# ESP32_with_USBC.net
KiCad netlist of a schematic drawn in Altium Designer
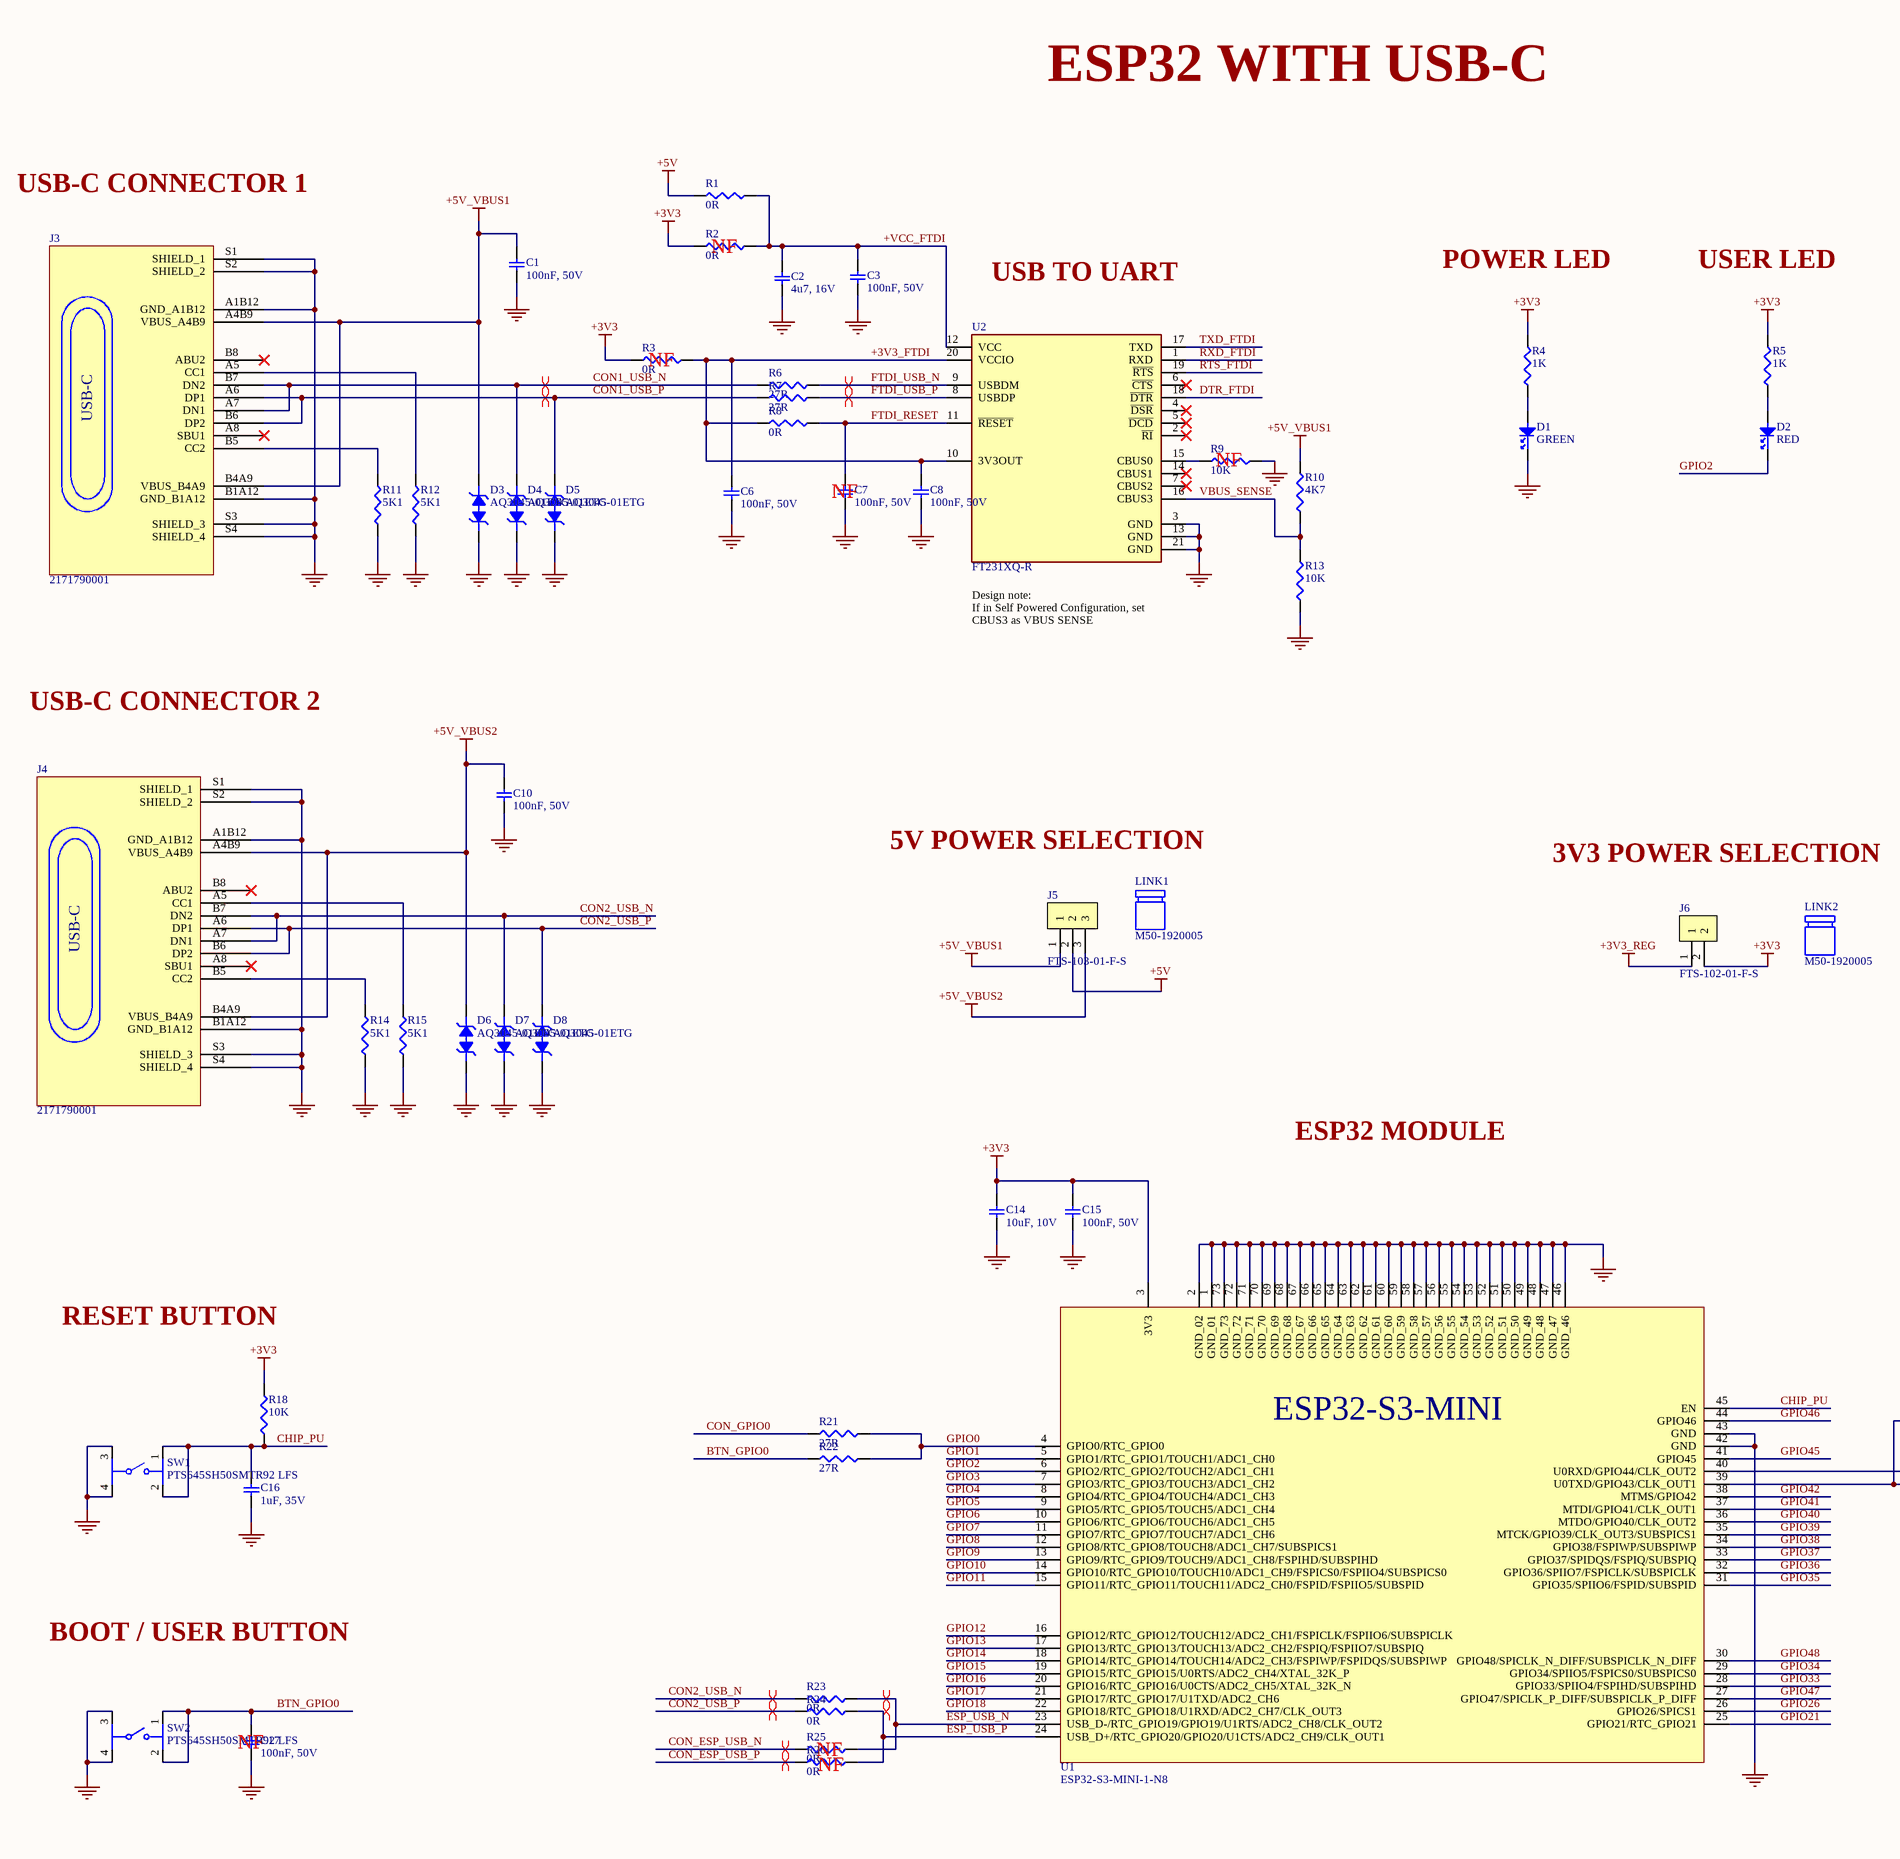
[diagram p0: ESP32 with USBC.SchDoc, left]
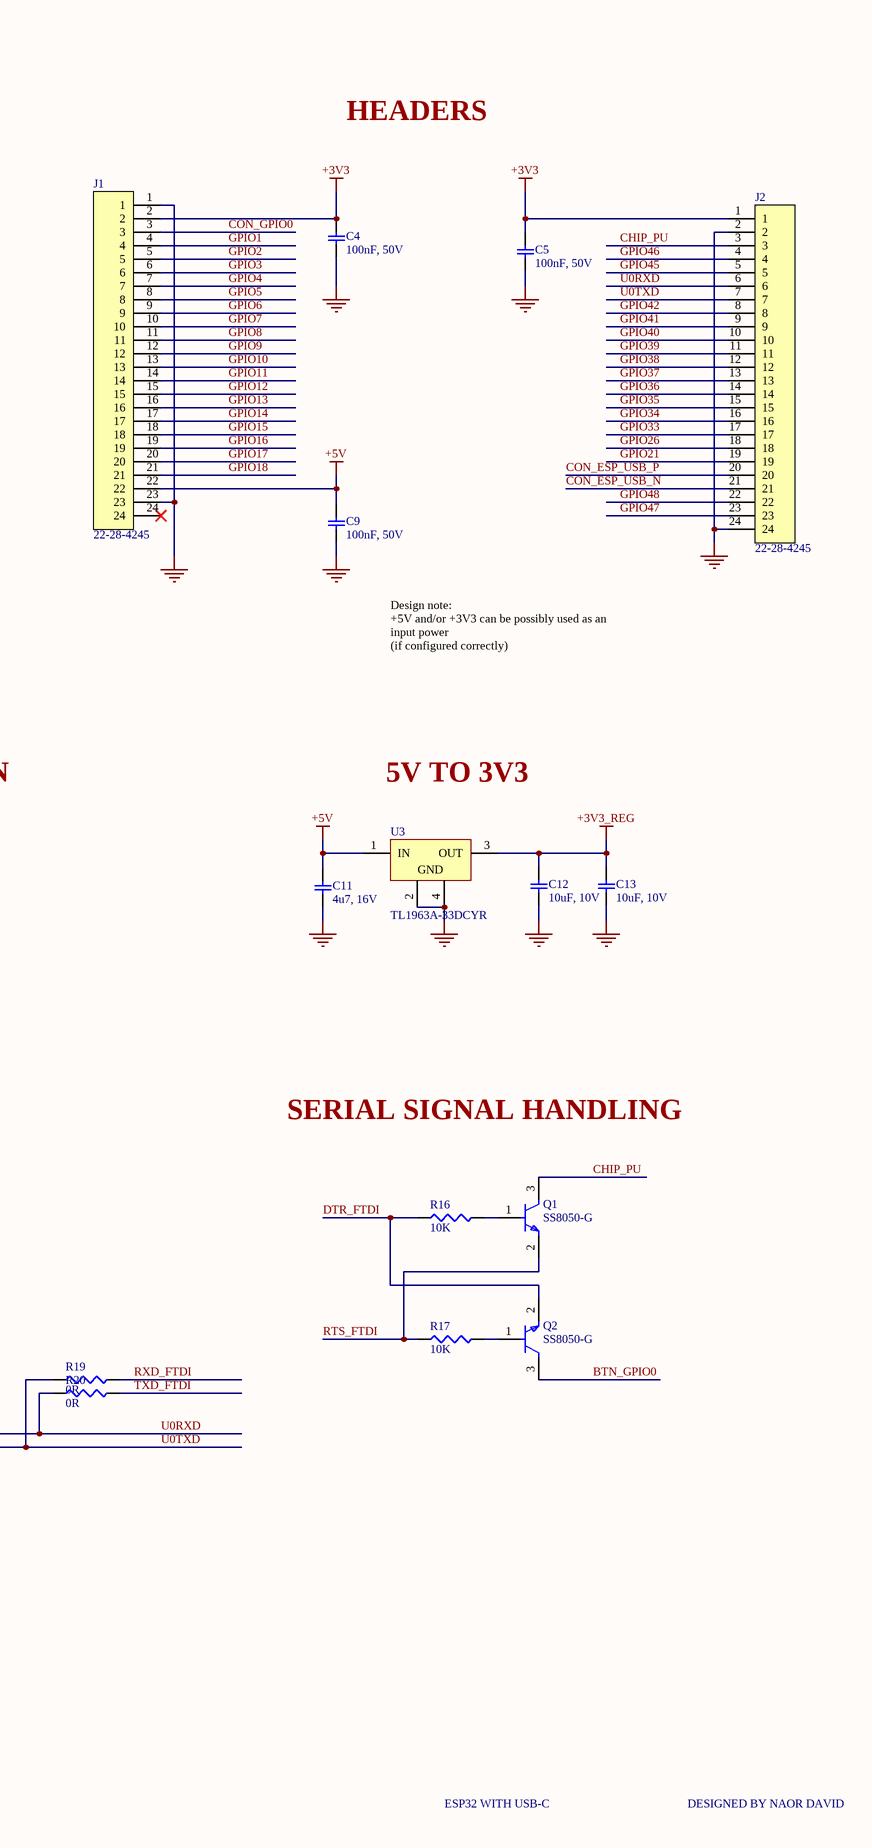
[diagram p1: ESP32 with USBC.SchDoc, right]

(export (version "E")
  (design (tool "Eeschema 10.0.6"))
  (components
    (comp (ref "C1")
      (value "100nF, 50V")
      (footprint "CAPC1005X65N")
      (description "CAP CER 0.1UF 50V X7R 0402")
      (fields
        (field (name "MANUFACTURER") "Samsung Electro-Mechanics")
        (field (name "MANUFACTURER PART NUMBER") "CL05B104KB54PNC")
      )
      (libsource (lib "Schlib") (part "CL05B104KB54PNC"))
    )
    (comp (ref "C2")
      (value "4u7, 16V")
      (footprint "CAPC1005X65N")
      (description "CAP CER 4.7UF 16V X5R 0402")
      (fields
        (field (name "MANUFACTURER") "Samsung Electro-Mechanics")
        (field (name "MANUFACTURER PART NUMBER") "CL05A475MO5NUNC")
      )
      (libsource (lib "Schlib") (part "CL05A475MO5NUNC"))
    )
    (comp (ref "C3")
      (value "100nF, 50V")
      (footprint "CAPC1005X65N")
      (description "CAP CER 0.1UF 50V X7R 0402")
      (fields
        (field (name "MANUFACTURER") "Samsung Electro-Mechanics")
        (field (name "MANUFACTURER PART NUMBER") "CL05B104KB54PNC")
      )
      (libsource (lib "Schlib") (part "CL05B104KB54PNC"))
    )
    (comp (ref "C4")
      (value "100nF, 50V")
      (footprint "CAPC1005X65N")
      (description "CAP CER 0.1UF 50V X7R 0402")
      (fields
        (field (name "MANUFACTURER") "Samsung Electro-Mechanics")
        (field (name "MANUFACTURER PART NUMBER") "CL05B104KB54PNC")
      )
      (libsource (lib "Schlib") (part "CL05B104KB54PNC"))
    )
    (comp (ref "C5")
      (value "100nF, 50V")
      (footprint "CAPC1005X65N")
      (description "CAP CER 0.1UF 50V X7R 0402")
      (fields
        (field (name "MANUFACTURER") "Samsung Electro-Mechanics")
        (field (name "MANUFACTURER PART NUMBER") "CL05B104KB54PNC")
      )
      (libsource (lib "Schlib") (part "CL05B104KB54PNC"))
    )
    (comp (ref "C6")
      (value "100nF, 50V")
      (footprint "CAPC1005X65N")
      (description "CAP CER 0.1UF 50V X7R 0402")
      (fields
        (field (name "MANUFACTURER") "Samsung Electro-Mechanics")
        (field (name "MANUFACTURER PART NUMBER") "CL05B104KB54PNC")
      )
      (libsource (lib "Schlib") (part "CL05B104KB54PNC"))
    )
    (comp (ref "C7")
      (value "100nF, 50V")
      (footprint "CAPC1005X65N")
      (description "CAP CER 0.1UF 50V X7R 0402")
      (fields
        (field (name "MANUFACTURER") "Samsung Electro-Mechanics")
        (field (name "MANUFACTURER PART NUMBER") "CL05B104KB54PNC")
      )
      (libsource (lib "Schlib") (part "CL05B104KB54PNC"))
    )
    (comp (ref "C8")
      (value "100nF, 50V")
      (footprint "CAPC1005X65N")
      (description "CAP CER 0.1UF 50V X7R 0402")
      (fields
        (field (name "MANUFACTURER") "Samsung Electro-Mechanics")
        (field (name "MANUFACTURER PART NUMBER") "CL05B104KB54PNC")
      )
      (libsource (lib "Schlib") (part "CL05B104KB54PNC"))
    )
    (comp (ref "C9")
      (value "100nF, 50V")
      (footprint "CAPC1005X65N")
      (description "CAP CER 0.1UF 50V X7R 0402")
      (fields
        (field (name "MANUFACTURER") "Samsung Electro-Mechanics")
        (field (name "MANUFACTURER PART NUMBER") "CL05B104KB54PNC")
      )
      (libsource (lib "Schlib") (part "CL05B104KB54PNC"))
    )
    (comp (ref "C10")
      (value "100nF, 50V")
      (footprint "CAPC1005X65N")
      (description "CAP CER 0.1UF 50V X7R 0402")
      (fields
        (field (name "MANUFACTURER") "Samsung Electro-Mechanics")
        (field (name "MANUFACTURER PART NUMBER") "CL05B104KB54PNC")
      )
      (libsource (lib "Schlib") (part "CL05B104KB54PNC"))
    )
    (comp (ref "C11")
      (value "4u7, 16V")
      (footprint "CAPC1005X65N")
      (description "CAP CER 4.7UF 16V X5R 0402")
      (fields
        (field (name "MANUFACTURER") "Samsung Electro-Mechanics")
        (field (name "MANUFACTURER PART NUMBER") "CL05A475MO5NUNC")
      )
      (libsource (lib "Schlib") (part "CL05A475MO5NUNC"))
    )
    (comp (ref "C12")
      (value "10uF, 10V")
      (footprint "CAPC1005X65N")
      (description "CAP CER 10UF 10V X5R 0402")
      (fields
        (field (name "MANUFACTURER") "Samsung Electro-Mechanics")
        (field (name "MANUFACTURER PART NUMBER") "CL05A106MP8NUB8")
      )
      (libsource (lib "Schlib") (part "CL05A106MP8NUB8"))
    )
    (comp (ref "C13")
      (value "10uF, 10V")
      (footprint "CAPC1005X65N")
      (description "CAP CER 10UF 10V X5R 0402")
      (fields
        (field (name "MANUFACTURER") "Samsung Electro-Mechanics")
        (field (name "MANUFACTURER PART NUMBER") "CL05A106MP8NUB8")
      )
      (libsource (lib "Schlib") (part "CL05A106MP8NUB8"))
    )
    (comp (ref "C14")
      (value "10uF, 10V")
      (footprint "CAPC1005X65N")
      (description "CAP CER 10UF 10V X5R 0402")
      (fields
        (field (name "MANUFACTURER") "Samsung Electro-Mechanics")
        (field (name "MANUFACTURER PART NUMBER") "CL05A106MP8NUB8")
      )
      (libsource (lib "Schlib") (part "CL05A106MP8NUB8"))
    )
    (comp (ref "C15")
      (value "100nF, 50V")
      (footprint "CAPC1005X65N")
      (description "CAP CER 0.1UF 50V X7R 0402")
      (fields
        (field (name "MANUFACTURER") "Samsung Electro-Mechanics")
        (field (name "MANUFACTURER PART NUMBER") "CL05B104KB54PNC")
      )
      (libsource (lib "Schlib") (part "CL05B104KB54PNC"))
    )
    (comp (ref "C16")
      (value "1uF, 35V")
      (footprint "CAPC1005X65N")
      (description "CAP CER 1UF 35V X5R 0402")
      (fields
        (field (name "MANUFACTURER") "Samsung Electro-Mechanics")
        (field (name "MANUFACTURER PART NUMBER") "CL05A105KL5NRNC")
      )
      (libsource (lib "Schlib") (part "CL05A105KL5NRNC"))
    )
    (comp (ref "C17")
      (value "100nF, 50V")
      (footprint "CAPC1005X65N")
      (description "CAP CER 0.1UF 50V X7R 0402")
      (fields
        (field (name "MANUFACTURER") "Samsung Electro-Mechanics")
        (field (name "MANUFACTURER PART NUMBER") "CL05B104KB54PNC")
      )
      (libsource (lib "Schlib") (part "CL05B104KB54PNC"))
    )
    (comp (ref "D1")
      (value "GREEN")
      (footprint "LED0402G")
      (description "LED GREEN 0402 SMD")
      (fields
        (field (name "MANUFACTURER") "Vishay")
        (field (name "MANUFACTURER PART NUMBER") "VLMTG1500-GS08")
      )
      (libsource (lib "Schlib") (part "VLMTG1500-GS08"))
    )
    (comp (ref "D2")
      (value "RED")
      (footprint "LED0402R")
      (description "LED RED 0402 SMD")
      (fields
        (field (name "MANUFACTURER") "Vishay")
        (field (name "MANUFACTURER PART NUMBER") "VLMS1500-GS08")
      )
      (libsource (lib "Schlib") (part "VLMS1500-GS08"))
    )
    (comp (ref "D3")
      (value "AQ3045-01ETG")
      (footprint "SOD882")
      (description "TVS DIODE 5.3VWM 12VC SOD882")
      (fields (field (name "MANUFACTURER") "Littelfuse") (field (name "LCSC PART NUMBER") "C3710326"))
      (libsource (lib "Schlib") (part "AQ3045-01ETG"))
    )
    (comp (ref "D4")
      (value "AQ3045-01ETG")
      (footprint "SOD882")
      (description "TVS DIODE 5.3VWM 12VC SOD882")
      (fields (field (name "MANUFACTURER") "Littelfuse") (field (name "LCSC PART NUMBER") "C3710326"))
      (libsource (lib "Schlib") (part "AQ3045-01ETG"))
    )
    (comp (ref "D5")
      (value "AQ3045-01ETG")
      (footprint "SOD882")
      (description "TVS DIODE 5.3VWM 12VC SOD882")
      (fields (field (name "MANUFACTURER") "Littelfuse") (field (name "LCSC PART NUMBER") "C3710326"))
      (libsource (lib "Schlib") (part "AQ3045-01ETG"))
    )
    (comp (ref "D6")
      (value "AQ3045-01ETG")
      (footprint "SOD882")
      (description "TVS DIODE 5.3VWM 12VC SOD882")
      (fields (field (name "MANUFACTURER") "Littelfuse") (field (name "LCSC PART NUMBER") "C3710326"))
      (libsource (lib "Schlib") (part "AQ3045-01ETG"))
    )
    (comp (ref "D7")
      (value "AQ3045-01ETG")
      (footprint "SOD882")
      (description "TVS DIODE 5.3VWM 12VC SOD882")
      (fields (field (name "MANUFACTURER") "Littelfuse") (field (name "LCSC PART NUMBER") "C3710326"))
      (libsource (lib "Schlib") (part "AQ3045-01ETG"))
    )
    (comp (ref "D8")
      (value "AQ3045-01ETG")
      (footprint "SOD882")
      (description "TVS DIODE 5.3VWM 12VC SOD882")
      (fields (field (name "MANUFACTURER") "Littelfuse") (field (name "LCSC PART NUMBER") "C3710326"))
      (libsource (lib "Schlib") (part "AQ3045-01ETG"))
    )
    (comp (ref "J1")
      (value "22-28-4245")
      (footprint "HDR_1X24_2.54MM")
      (description "CONN HEADER VERT 24POS 2.54MM")
      (fields (field (name "MANUFACTURER") "Molex") (field (name "LCSC PART NUMBER") "C7145888"))
      (libsource (lib "") (part "22-28-4245_1"))
    )
    (comp (ref "J2")
      (value "22-28-4245")
      (footprint "HDR_1X24_2.54MM")
      (description "CONN HEADER VERT 24POS 2.54MM")
      (fields (field (name "MANUFACTURER") "Molex") (field (name "LCSC PART NUMBER") "C7145888"))
      (libsource (lib "Schlib") (part "22-28-4245"))
    )
    (comp (ref "J3")
      (value "2171790001")
      (footprint "FP-2171790001-MFG")
      (description "CONN RCP USB2.0 TYP C 24P SMD RA")
      (fields (field (name "MANUFACTURER") "Molex") (field (name "MANUFACTURER PART NUMBER") "217179-0001"))
      (libsource (lib "Schlib") (part "217179-0001"))
    )
    (comp (ref "J4")
      (value "2171790001")
      (footprint "FP-2171790001-MFG")
      (description "CONN RCP USB2.0 TYP C 24P SMD RA")
      (fields (field (name "MANUFACTURER") "Molex") (field (name "MANUFACTURER PART NUMBER") "217179-0001"))
      (libsource (lib "Schlib") (part "217179-0001"))
    )
    (comp (ref "J5")
      (value "FTS-103-01-F-S")
      (footprint "HDR_1X3_1.27MM")
      (description "CONN HEADER VERT 3POS 1.27MM")
      (fields (field (name "MANUFACTURER") "Samtec") (field (name "LCSC PART NUMBER") "C3333578"))
      (libsource (lib "Schlib") (part "FTS-103-01-F-S"))
    )
    (comp (ref "J6")
      (value "FTS-102-01-F-S")
      (footprint "HDR_1X2_1.27MM")
      (description "CONN HEADER VERT 2POS 1.27MM")
      (fields (field (name "MANUFACTURER") "Samtec") (field (name "LCSC PART NUMBER") "C6045317"))
      (libsource (lib "Schlib") (part "FTS-102-01-F-S"))
    )
    (comp (ref "LINK1")
      (value "M50-1920005")
      (description "CONN SHUNT 1.27MM RED")
      (fields (field (name "MANUFACTURER") "Harwin") (field (name "LCSC PART NUMBER") "C6985646"))
      (libsource (lib "Schlib") (part "M50-1920005"))
    )
    (comp (ref "LINK2")
      (value "M50-1920005")
      (description "CONN SHUNT 1.27MM RED")
      (fields (field (name "MANUFACTURER") "Harwin") (field (name "LCSC PART NUMBER") "C6985646"))
      (libsource (lib "Schlib") (part "M50-1920005"))
    )
    (comp (ref "Q1")
      (value "SS8050-G")
      (footprint "FP-SS8050-G-IPC_B")
      (description "TRANS NPN 25V 1.5A SOT-23-3")
      (fields (field (name "MANUFACTURER") "Comchip") (field (name "LCSC PART NUMBER") "C164886"))
      (libsource (lib "Schlib") (part "SS8050-G"))
    )
    (comp (ref "Q2")
      (value "SS8050-G")
      (footprint "FP-SS8050-G-IPC_B")
      (description "TRANS NPN 25V 1.5A SOT-23-3")
      (fields (field (name "MANUFACTURER") "Comchip") (field (name "LCSC PART NUMBER") "C164886"))
      (libsource (lib "Schlib") (part "SS8050-G"))
    )
    (comp (ref "R1")
      (value "0R")
      (footprint "RESC1005X37N")
      (description "RES 0 OHM JUMPER 1/16W 0402")
      (fields
        (field (name "MANUFACTURER") "Yageo Group")
        (field (name "MANUFACTURER PART NUMBER") "RC0402JR-070RL")
      )
      (libsource (lib "Schlib") (part "RC0402JR-070RL"))
    )
    (comp (ref "R2")
      (value "0R")
      (footprint "RESC1005X37N")
      (description "RES 0 OHM JUMPER 1/16W 0402")
      (fields
        (field (name "MANUFACTURER") "Yageo Group")
        (field (name "MANUFACTURER PART NUMBER") "RC0402JR-070RL")
      )
      (libsource (lib "Schlib") (part "RC0402JR-070RL"))
    )
    (comp (ref "R3")
      (value "0R")
      (footprint "RESC1005X37N")
      (description "RES 0 OHM JUMPER 1/16W 0402")
      (fields
        (field (name "MANUFACTURER") "Yageo Group")
        (field (name "MANUFACTURER PART NUMBER") "RC0402JR-070RL")
      )
      (libsource (lib "Schlib") (part "RC0402JR-070RL"))
    )
    (comp (ref "R4")
      (value "1K")
      (footprint "RESC1005X37N")
      (description "RES 1K OHM 1% 1/16W 0402")
      (fields
        (field (name "MANUFACTURER") "Yageo Group")
        (field (name "MANUFACTURER PART NUMBER") "RC0402FR-071KL")
      )
      (libsource (lib "Schlib") (part "RC0402FR-071KL"))
    )
    (comp (ref "R5")
      (value "1K")
      (footprint "RESC1005X37N")
      (description "RES 1K OHM 1% 1/16W 0402")
      (fields
        (field (name "MANUFACTURER") "Yageo Group")
        (field (name "MANUFACTURER PART NUMBER") "RC0402FR-071KL")
      )
      (libsource (lib "Schlib") (part "RC0402FR-071KL"))
    )
    (comp (ref "R6")
      (value "27R")
      (footprint "RESC1005X37N")
      (description "RES 27 OHM 1% 1/16W 0402")
      (fields
        (field (name "MANUFACTURER") "Yageo Group")
        (field (name "MANUFACTURER PART NUMBER") "RC0402FR-0727RL")
      )
      (libsource (lib "Schlib") (part "RC0402FR-0727RL"))
    )
    (comp (ref "R7")
      (value "27R")
      (footprint "RESC1005X37N")
      (description "RES 27 OHM 1% 1/16W 0402")
      (fields
        (field (name "MANUFACTURER") "Yageo Group")
        (field (name "MANUFACTURER PART NUMBER") "RC0402FR-0727RL")
      )
      (libsource (lib "Schlib") (part "RC0402FR-0727RL"))
    )
    (comp (ref "R8")
      (value "0R")
      (footprint "RESC1005X37N")
      (description "RES 0 OHM JUMPER 1/16W 0402")
      (fields
        (field (name "MANUFACTURER") "Yageo Group")
        (field (name "MANUFACTURER PART NUMBER") "RC0402JR-070RL")
      )
      (libsource (lib "Schlib") (part "RC0402JR-070RL"))
    )
    (comp (ref "R9")
      (value "10K")
      (footprint "RESC1005X37N")
      (description "RES SMD 10K OHM 1% 1/16W 0402")
      (fields
        (field (name "MANUFACTURER") "Yageo Group")
        (field (name "MANUFACTURER PART NUMBER") "AC0402FR-0710KL")
      )
      (libsource (lib "Schlib") (part "AC0402FR-0710KL"))
    )
    (comp (ref "R10")
      (value "4K7")
      (footprint "RESC1005X37N")
      (description "RES 4.7K OHM 1% 1/16W 0402")
      (fields
        (field (name "MANUFACTURER") "Yageo Group")
        (field (name "MANUFACTURER PART NUMBER") "RC0402FR-074K7L")
      )
      (libsource (lib "Schlib") (part "RC0402FR-074K7L"))
    )
    (comp (ref "R11")
      (value "5K1")
      (footprint "RESC1005X37N")
      (description "RES SMD 5.1K OHM 1% 1/16W 0402")
      (fields
        (field (name "MANUFACTURER") "Yageo Group")
        (field (name "MANUFACTURER PART NUMBER") "AC0402FR-075K1L")
      )
      (libsource (lib "Schlib") (part "AC0402FR-075K1L"))
    )
    (comp (ref "R12")
      (value "5K1")
      (footprint "RESC1005X37N")
      (description "RES SMD 5.1K OHM 1% 1/16W 0402")
      (fields
        (field (name "MANUFACTURER") "Yageo Group")
        (field (name "MANUFACTURER PART NUMBER") "AC0402FR-075K1L")
      )
      (libsource (lib "Schlib") (part "AC0402FR-075K1L"))
    )
    (comp (ref "R13")
      (value "10K")
      (footprint "RESC1005X37N")
      (description "RES SMD 10K OHM 1% 1/16W 0402")
      (fields
        (field (name "MANUFACTURER") "Yageo Group")
        (field (name "MANUFACTURER PART NUMBER") "AC0402FR-0710KL")
      )
      (libsource (lib "Schlib") (part "AC0402FR-0710KL"))
    )
    (comp (ref "R14")
      (value "5K1")
      (footprint "RESC1005X37N")
      (description "RES SMD 5.1K OHM 1% 1/16W 0402")
      (fields
        (field (name "MANUFACTURER") "Yageo Group")
        (field (name "MANUFACTURER PART NUMBER") "AC0402FR-075K1L")
      )
      (libsource (lib "Schlib") (part "AC0402FR-075K1L"))
    )
    (comp (ref "R15")
      (value "5K1")
      (footprint "RESC1005X37N")
      (description "RES SMD 5.1K OHM 1% 1/16W 0402")
      (fields
        (field (name "MANUFACTURER") "Yageo Group")
        (field (name "MANUFACTURER PART NUMBER") "AC0402FR-075K1L")
      )
      (libsource (lib "Schlib") (part "AC0402FR-075K1L"))
    )
    (comp (ref "R16")
      (value "10K")
      (footprint "RESC1005X37N")
      (description "RES SMD 10K OHM 1% 1/16W 0402")
      (fields
        (field (name "MANUFACTURER") "Yageo Group")
        (field (name "MANUFACTURER PART NUMBER") "AC0402FR-0710KL")
      )
      (libsource (lib "Schlib") (part "AC0402FR-0710KL"))
    )
    (comp (ref "R17")
      (value "10K")
      (footprint "RESC1005X37N")
      (description "RES SMD 10K OHM 1% 1/16W 0402")
      (fields
        (field (name "MANUFACTURER") "Yageo Group")
        (field (name "MANUFACTURER PART NUMBER") "AC0402FR-0710KL")
      )
      (libsource (lib "Schlib") (part "AC0402FR-0710KL"))
    )
    (comp (ref "R18")
      (value "10K")
      (footprint "RESC1005X37N")
      (description "RES SMD 10K OHM 1% 1/16W 0402")
      (fields
        (field (name "MANUFACTURER") "Yageo Group")
        (field (name "MANUFACTURER PART NUMBER") "AC0402FR-0710KL")
      )
      (libsource (lib "Schlib") (part "AC0402FR-0710KL"))
    )
    (comp (ref "R19")
      (value "0R")
      (footprint "RESC1005X37N")
      (description "RES 0 OHM JUMPER 1/16W 0402")
      (fields
        (field (name "MANUFACTURER") "Yageo Group")
        (field (name "MANUFACTURER PART NUMBER") "RC0402JR-070RL")
      )
      (libsource (lib "Schlib") (part "RC0402JR-070RL"))
    )
    (comp (ref "R20")
      (value "0R")
      (footprint "RESC1005X37N")
      (description "RES 0 OHM JUMPER 1/16W 0402")
      (fields
        (field (name "MANUFACTURER") "Yageo Group")
        (field (name "MANUFACTURER PART NUMBER") "RC0402JR-070RL")
      )
      (libsource (lib "Schlib") (part "RC0402JR-070RL"))
    )
    (comp (ref "R21")
      (value "27R")
      (footprint "RESC1005X37N")
      (description "RES 27 OHM 1% 1/16W 0402")
      (fields
        (field (name "MANUFACTURER") "Yageo Group")
        (field (name "MANUFACTURER PART NUMBER") "RC0402FR-0727RL")
      )
      (libsource (lib "Schlib") (part "RC0402FR-0727RL"))
    )
    (comp (ref "R22")
      (value "27R")
      (footprint "RESC1005X37N")
      (description "RES 27 OHM 1% 1/16W 0402")
      (fields
        (field (name "MANUFACTURER") "Yageo Group")
        (field (name "MANUFACTURER PART NUMBER") "RC0402FR-0727RL")
      )
      (libsource (lib "Schlib") (part "RC0402FR-0727RL"))
    )
    (comp (ref "R23")
      (value "0R")
      (footprint "RESC1005X37N")
      (description "RES 0 OHM JUMPER 1/16W 0402")
      (fields
        (field (name "MANUFACTURER") "Yageo Group")
        (field (name "MANUFACTURER PART NUMBER") "RC0402JR-070RL")
      )
      (libsource (lib "Schlib") (part "RC0402JR-070RL"))
    )
    (comp (ref "R24")
      (value "0R")
      (footprint "RESC1005X37N")
      (description "RES 0 OHM JUMPER 1/16W 0402")
      (fields
        (field (name "MANUFACTURER") "Yageo Group")
        (field (name "MANUFACTURER PART NUMBER") "RC0402JR-070RL")
      )
      (libsource (lib "Schlib") (part "RC0402JR-070RL"))
    )
    (comp (ref "R25")
      (value "0R")
      (footprint "RESC1005X37N")
      (description "RES 0 OHM JUMPER 1/16W 0402")
      (fields
        (field (name "MANUFACTURER") "Yageo Group")
        (field (name "MANUFACTURER PART NUMBER") "RC0402JR-070RL")
      )
      (libsource (lib "Schlib") (part "RC0402JR-070RL"))
    )
    (comp (ref "R26")
      (value "0R")
      (footprint "RESC1005X37N")
      (description "RES 0 OHM JUMPER 1/16W 0402")
      (fields
        (field (name "MANUFACTURER") "Yageo Group")
        (field (name "MANUFACTURER PART NUMBER") "RC0402JR-070RL")
      )
      (libsource (lib "Schlib") (part "RC0402JR-070RL"))
    )
    (comp (ref "SW1")
      (value "PTS645SH50SMTR92 LFS")
      (footprint "FP-PTS645SH50SMTR92LFS-MFG")
      (description "SWITCH TACTILE SPST-NO 0.05A 12V")
      (fields
        (field (name "MANUFACTURER") "C&K Components")
        (field (name "MANUFACTURER PART NUMBER") "PTS645SH50SMTR92LFS")
      )
      (libsource (lib "Schlib") (part "PTS645SH50SMTR92LFS"))
    )
    (comp (ref "SW2")
      (value "PTS645SH50SMTR92 LFS")
      (footprint "FP-PTS645SH50SMTR92LFS-MFG")
      (description "SWITCH TACTILE SPST-NO 0.05A 12V")
      (fields
        (field (name "MANUFACTURER") "C&K Components")
        (field (name "MANUFACTURER PART NUMBER") "PTS645SH50SMTR92LFS")
      )
      (libsource (lib "Schlib") (part "PTS645SH50SMTR92LFS"))
    )
    (comp (ref "U1")
      (value "ESP32-S3-MINI-1-N8")
      (footprint "XCVR_ESP32-S3-MINI-1-N8")
      (description "SMD module, ESP32-S3FN8, 8 MB SPI flash, PCB antenna")
      (fields (field (name "MANUFACTURER") "Espressif Systems") (field (name "LCSC PART NUMBER") "C2913206"))
      (libsource (lib "Schlib") (part "ESP32-S3-MINI-1-N8"))
    )
    (comp (ref "U2")
      (value "FT231XQ-R")
      (footprint "FP-QFN-20-IPC_B")
      (description "IC USB SERIAL FULL UART 20QFN")
      (fields (field (name "MANUFACTURER") "FTDI") (field (name "LCSC PART NUMBER") "C132159"))
      (libsource (lib "Schlib") (part "FT231XQ-R"))
    )
    (comp (ref "U3")
      (value "TL1963A-33DCYR")
      (footprint "DCY0004A_N")
      (description "IC REG LIN 3.3V 1.5A SOT-223-4")
      (fields (field (name "MANUFACTURER") "Texas Instruments") (field (name "LCSC PART NUMBER") "C181262"))
      (libsource (lib "Schlib") (part "TL1963A-33DCYR"))
    )
  )
  (nets
    (net (code "1") (name "+3V3") (class "Default")
      (node (ref "C14") (pin "2") (pinfunction "2_2") (pintype "passive"))
      (node (ref "C15") (pin "2") (pinfunction "2_2") (pintype "passive"))
      (node (ref "C4") (pin "2") (pinfunction "2_2") (pintype "passive"))
      (node (ref "C5") (pin "2") (pinfunction "2_2") (pintype "passive"))
      (node (ref "J1") (pin "2") (pinfunction "2_2") (pintype "passive"))
      (node (ref "J2") (pin "1") (pinfunction "1_1") (pintype "passive"))
      (node (ref "J6") (pin "2") (pinfunction "2_2") (pintype "passive"))
      (node (ref "R18") (pin "2") (pinfunction "2_2") (pintype "passive"))
      (node (ref "R2") (pin "1") (pinfunction "1_1") (pintype "passive"))
      (node (ref "R3") (pin "1") (pinfunction "1_1") (pintype "passive"))
      (node (ref "R4") (pin "2") (pinfunction "2_2") (pintype "passive"))
      (node (ref "R5") (pin "2") (pinfunction "2_2") (pintype "passive"))
      (node (ref "U1") (pin "3") (pinfunction "3V3_3") (pintype "passive"))
    )
    (net (code "2") (name "+3V3_REG") (class "Default")
      (node (ref "C12") (pin "2") (pinfunction "2_2") (pintype "passive"))
      (node (ref "C13") (pin "2") (pinfunction "2_2") (pintype "passive"))
      (node (ref "J6") (pin "1") (pinfunction "1_1") (pintype "passive"))
      (node (ref "U3") (pin "3") (pinfunction "OUT_3") (pintype "power_in"))
    )
    (net (code "3") (name "+5V") (class "Default")
      (node (ref "C11") (pin "2") (pinfunction "2_2") (pintype "passive"))
      (node (ref "C9") (pin "2") (pinfunction "2_2") (pintype "passive"))
      (node (ref "J1") (pin "22") (pinfunction "22_22") (pintype "passive"))
      (node (ref "J5") (pin "2") (pinfunction "2_2") (pintype "passive"))
      (node (ref "R1") (pin "1") (pinfunction "1_1") (pintype "passive"))
      (node (ref "U3") (pin "1") (pinfunction "IN_1") (pintype "power_in"))
    )
    (net (code "4") (name "+5V_VBUS1") (class "Default")
      (node (ref "C1") (pin "2") (pinfunction "2_2") (pintype "passive"))
      (node (ref "D3") (pin "1") (pinfunction "1_1") (pintype "passive"))
      (node (ref "J3") (pin "A4B9") (pinfunction "VBUS_A4B9_A4B9") (pintype "passive"))
      (node (ref "J3") (pin "B4A9") (pinfunction "VBUS_B4A9_B4A9") (pintype "passive"))
      (node (ref "J5") (pin "1") (pinfunction "1_1") (pintype "passive"))
      (node (ref "R10") (pin "2") (pinfunction "2_2") (pintype "passive"))
    )
    (net (code "5") (name "+5V_VBUS2") (class "Default")
      (node (ref "C10") (pin "2") (pinfunction "2_2") (pintype "passive"))
      (node (ref "D6") (pin "1") (pinfunction "1_1") (pintype "passive"))
      (node (ref "J4") (pin "A4B9") (pinfunction "VBUS_A4B9_A4B9") (pintype "passive"))
      (node (ref "J4") (pin "B4A9") (pinfunction "VBUS_B4A9_B4A9") (pintype "passive"))
      (node (ref "J5") (pin "3") (pinfunction "3_3") (pintype "passive"))
    )
    (net (code "6") (name "/+3V3_FTDI") (class "Default")
      (node (ref "C6") (pin "2") (pinfunction "2_2") (pintype "passive"))
      (node (ref "C8") (pin "2") (pinfunction "2_2") (pintype "passive"))
      (node (ref "R3") (pin "2") (pinfunction "2_2") (pintype "passive"))
      (node (ref "R8") (pin "1") (pinfunction "1_1") (pintype "passive"))
      (node (ref "U2") (pin "10") (pinfunction "3V3OUT_10") (pintype "passive"))
      (node (ref "U2") (pin "20") (pinfunction "VCCIO_20") (pintype "passive"))
    )
    (net (code "7") (name "/+VCC_FTDI") (class "Default")
      (node (ref "C2") (pin "2") (pinfunction "2_2") (pintype "passive"))
      (node (ref "C3") (pin "2") (pinfunction "2_2") (pintype "passive"))
      (node (ref "R1") (pin "2") (pinfunction "2_2") (pintype "passive"))
      (node (ref "R2") (pin "2") (pinfunction "2_2") (pintype "passive"))
      (node (ref "U2") (pin "12") (pinfunction "VCC_12") (pintype "passive"))
    )
    (net (code "8") (name "/BTN_GPIO0") (class "Default")
      (node (ref "C17") (pin "2") (pinfunction "2_2") (pintype "passive"))
      (node (ref "Q2") (pin "3") (pinfunction "C_3") (pintype "passive"))
      (node (ref "R22") (pin "1") (pinfunction "1_1") (pintype "passive"))
      (node (ref "SW2") (pin "1") (pinfunction "1_1") (pintype "passive"))
      (node (ref "SW2") (pin "2") (pinfunction "2_2") (pintype "passive"))
    )
    (net (code "9") (name "/CHIP_PU") (class "Default")
      (node (ref "C16") (pin "1") (pinfunction "1_1") (pintype "passive"))
      (node (ref "J2") (pin "3") (pinfunction "3_3") (pintype "passive"))
      (node (ref "Q1") (pin "3") (pinfunction "C_3") (pintype "passive"))
      (node (ref "R18") (pin "1") (pinfunction "1_1") (pintype "passive"))
      (node (ref "SW1") (pin "1") (pinfunction "1_1") (pintype "passive"))
      (node (ref "SW1") (pin "2") (pinfunction "2_2") (pintype "passive"))
      (node (ref "U1") (pin "45") (pinfunction "EN_45") (pintype "passive"))
    )
    (net (code "10") (name "/CON1_USB_N") (class "Default")
      (node (ref "D4") (pin "1") (pinfunction "1_1") (pintype "passive"))
      (node (ref "J3") (pin "A7") (pinfunction "DN1_A7") (pintype "passive"))
      (node (ref "J3") (pin "B7") (pinfunction "DN2_B7") (pintype "passive"))
      (node (ref "R6") (pin "1") (pinfunction "1_1") (pintype "passive"))
    )
    (net (code "11") (name "/CON1_USB_P") (class "Default")
      (node (ref "D5") (pin "1") (pinfunction "1_1") (pintype "passive"))
      (node (ref "J3") (pin "A6") (pinfunction "DP1_A6") (pintype "passive"))
      (node (ref "J3") (pin "B6") (pinfunction "DP2_B6") (pintype "passive"))
      (node (ref "R7") (pin "1") (pinfunction "1_1") (pintype "passive"))
    )
    (net (code "12") (name "/CON2_USB_N") (class "Default")
      (node (ref "D7") (pin "1") (pinfunction "1_1") (pintype "passive"))
      (node (ref "J4") (pin "A7") (pinfunction "DN1_A7") (pintype "passive"))
      (node (ref "J4") (pin "B7") (pinfunction "DN2_B7") (pintype "passive"))
      (node (ref "R23") (pin "1") (pinfunction "1_1") (pintype "passive"))
    )
    (net (code "13") (name "/CON2_USB_P") (class "Default")
      (node (ref "D8") (pin "1") (pinfunction "1_1") (pintype "passive"))
      (node (ref "J4") (pin "A6") (pinfunction "DP1_A6") (pintype "passive"))
      (node (ref "J4") (pin "B6") (pinfunction "DP2_B6") (pintype "passive"))
      (node (ref "R24") (pin "1") (pinfunction "1_1") (pintype "passive"))
    )
    (net (code "14") (name "/CON_ESP_USB_N") (class "Default")
      (node (ref "J2") (pin "21") (pinfunction "21_21") (pintype "passive"))
      (node (ref "R25") (pin "1") (pinfunction "1_1") (pintype "passive"))
    )
    (net (code "15") (name "/CON_ESP_USB_P") (class "Default")
      (node (ref "J2") (pin "20") (pinfunction "20_20") (pintype "passive"))
      (node (ref "R26") (pin "1") (pinfunction "1_1") (pintype "passive"))
    )
    (net (code "16") (name "/CON_GPIO0") (class "Default")
      (node (ref "J1") (pin "3") (pinfunction "3_3") (pintype "passive"))
      (node (ref "R21") (pin "1") (pinfunction "1_1") (pintype "passive"))
    )
    (net (code "17") (name "/DTR_FTDI") (class "Default")
      (node (ref "Q2") (pin "2") (pinfunction "E_2") (pintype "passive"))
      (node (ref "R16") (pin "2") (pinfunction "2_2") (pintype "passive"))
      (node (ref "U2") (pin "18") (pinfunction "~{DTR}_18") (pintype "passive"))
    )
    (net (code "18") (name "/ESP_USB_N") (class "Default")
      (node (ref "R23") (pin "2") (pinfunction "2_2") (pintype "passive"))
      (node (ref "R25") (pin "2") (pinfunction "2_2") (pintype "passive"))
      (node (ref "U1") (pin "23") (pinfunction "USB_D-/RTC_GPIO19/GPIO19/U1RTS/ADC2_CH8/CLK_OUT2_23") (pintype "passive"))
    )
    (net (code "19") (name "/ESP_USB_P") (class "Default")
      (node (ref "R24") (pin "2") (pinfunction "2_2") (pintype "passive"))
      (node (ref "R26") (pin "2") (pinfunction "2_2") (pintype "passive"))
      (node (ref "U1") (pin "24") (pinfunction "USB_D+/RTC_GPIO20/GPIO20/U1CTS/ADC2_CH9/CLK_OUT1_24") (pintype "passive"))
    )
    (net (code "20") (name "/FTDI_RESET") (class "Default")
      (node (ref "C7") (pin "2") (pinfunction "2_2") (pintype "passive"))
      (node (ref "R8") (pin "2") (pinfunction "2_2") (pintype "passive"))
      (node (ref "U2") (pin "11") (pinfunction "~{RESET}_11") (pintype "passive"))
    )
    (net (code "21") (name "/FTDI_USB_N") (class "Default")
      (node (ref "R6") (pin "2") (pinfunction "2_2") (pintype "passive"))
      (node (ref "U2") (pin "9") (pinfunction "USBDM_9") (pintype "passive"))
    )
    (net (code "22") (name "/FTDI_USB_P") (class "Default")
      (node (ref "R7") (pin "2") (pinfunction "2_2") (pintype "passive"))
      (node (ref "U2") (pin "8") (pinfunction "USBDP_8") (pintype "passive"))
    )
    (net (code "23") (name "/GPIO0") (class "Default")
      (node (ref "R21") (pin "2") (pinfunction "2_2") (pintype "passive"))
      (node (ref "R22") (pin "2") (pinfunction "2_2") (pintype "passive"))
      (node (ref "U1") (pin "4") (pinfunction "GPIO0/RTC_GPIO0_4") (pintype "passive"))
    )
    (net (code "24") (name "/GPIO1") (class "Default")
      (node (ref "J1") (pin "4") (pinfunction "4_4") (pintype "passive"))
      (node (ref "U1") (pin "5") (pinfunction "GPIO1/RTC_GPIO1/TOUCH1/ADC1_CH0_5") (pintype "passive"))
    )
    (net (code "25") (name "/GPIO2") (class "Default")
      (node (ref "D2") (pin "1") (pinfunction "1_1") (pintype "passive"))
      (node (ref "J1") (pin "5") (pinfunction "5_5") (pintype "passive"))
      (node (ref "U1") (pin "6") (pinfunction "GPIO2/RTC_GPIO2/TOUCH2/ADC1_CH1_6") (pintype "passive"))
    )
    (net (code "26") (name "/GPIO3") (class "Default")
      (node (ref "J1") (pin "6") (pinfunction "6_6") (pintype "passive"))
      (node (ref "U1") (pin "7") (pinfunction "GPIO3/RTC_GPIO3/TOUCH3/ADC1_CH2_7") (pintype "passive"))
    )
    (net (code "27") (name "/GPIO4") (class "Default")
      (node (ref "J1") (pin "7") (pinfunction "7_7") (pintype "passive"))
      (node (ref "U1") (pin "8") (pinfunction "GPIO4/RTC_GPIO4/TOUCH4/ADC1_CH3_8") (pintype "passive"))
    )
    (net (code "28") (name "/GPIO5") (class "Default")
      (node (ref "J1") (pin "8") (pinfunction "8_8") (pintype "passive"))
      (node (ref "U1") (pin "9") (pinfunction "GPIO5/RTC_GPIO5/TOUCH5/ADC1_CH4_9") (pintype "passive"))
    )
    (net (code "29") (name "/GPIO6") (class "Default")
      (node (ref "J1") (pin "9") (pinfunction "9_9") (pintype "passive"))
      (node (ref "U1") (pin "10") (pinfunction "GPIO6/RTC_GPIO6/TOUCH6/ADC1_CH5_10") (pintype "passive"))
    )
    (net (code "30") (name "/GPIO7") (class "Default")
      (node (ref "J1") (pin "10") (pinfunction "10_10") (pintype "passive"))
      (node (ref "U1") (pin "11") (pinfunction "GPIO7/RTC_GPIO7/TOUCH7/ADC1_CH6_11") (pintype "passive"))
    )
    (net (code "31") (name "/GPIO8") (class "Default")
      (node (ref "J1") (pin "11") (pinfunction "11_11") (pintype "passive"))
      (node (ref "U1") (pin "12") (pinfunction "GPIO8/RTC_GPIO8/TOUCH8/ADC1_CH7/SUBSPICS1_12") (pintype "passive"))
    )
    (net (code "32") (name "/GPIO9") (class "Default")
      (node (ref "J1") (pin "12") (pinfunction "12_12") (pintype "passive"))
      (node (ref "U1") (pin "13") (pinfunction "GPIO9/RTC_GPIO9/TOUCH9/ADC1_CH8/FSPIHD/SUBSPIHD_13") (pintype "passive"))
    )
    (net (code "33") (name "/GPIO10") (class "Default")
      (node (ref "J1") (pin "13") (pinfunction "13_13") (pintype "passive"))
      (node (ref "U1") (pin "14") (pinfunction "GPIO10/RTC_GPIO10/TOUCH10/ADC1_CH9/FSPICS0/FSPIIO4/SUBSPICS0_14") (pintype "passive"))
    )
    (net (code "34") (name "/GPIO11") (class "Default")
      (node (ref "J1") (pin "14") (pinfunction "14_14") (pintype "passive"))
      (node (ref "U1") (pin "15") (pinfunction "GPIO11/RTC_GPIO11/TOUCH11/ADC2_CH0/FSPID/FSPIIO5/SUBSPID_15") (pintype "passive"))
    )
    (net (code "35") (name "/GPIO12") (class "Default")
      (node (ref "J1") (pin "15") (pinfunction "15_15") (pintype "passive"))
      (node (ref "U1") (pin "16") (pinfunction "GPIO12/RTC_GPIO12/TOUCH12/ADC2_CH1/FSPICLK/FSPIIO6/SUBSPICLK_16") (pintype "passive"))
    )
    (net (code "36") (name "/GPIO13") (class "Default")
      (node (ref "J1") (pin "16") (pinfunction "16_16") (pintype "passive"))
      (node (ref "U1") (pin "17") (pinfunction "GPIO13/RTC_GPIO13/TOUCH13/ADC2_CH2/FSPIQ/FSPIIO7/SUBSPIQ_17") (pintype "passive"))
    )
    (net (code "37") (name "/GPIO14") (class "Default")
      (node (ref "J1") (pin "17") (pinfunction "17_17") (pintype "passive"))
      (node (ref "U1") (pin "18") (pinfunction "GPIO14/RTC_GPIO14/TOUCH14/ADC2_CH3/FSPIWP/FSPIDQS/SUBSPIWP_18") (pintype "passive"))
    )
    (net (code "38") (name "/GPIO15") (class "Default")
      (node (ref "J1") (pin "18") (pinfunction "18_18") (pintype "passive"))
      (node (ref "U1") (pin "19") (pinfunction "GPIO15/RTC_GPIO15/U0RTS/ADC2_CH4/XTAL_32K_P_19") (pintype "passive"))
    )
    (net (code "39") (name "/GPIO16") (class "Default")
      (node (ref "J1") (pin "19") (pinfunction "19_19") (pintype "passive"))
      (node (ref "U1") (pin "20") (pinfunction "GPIO16/RTC_GPIO16/U0CTS/ADC2_CH5/XTAL_32K_N_20") (pintype "passive"))
    )
    (net (code "40") (name "/GPIO17") (class "Default")
      (node (ref "J1") (pin "20") (pinfunction "20_20") (pintype "passive"))
      (node (ref "U1") (pin "21") (pinfunction "GPIO17/RTC_GPIO17/U1TXD/ADC2_CH6_21") (pintype "passive"))
    )
    (net (code "41") (name "/GPIO18") (class "Default")
      (node (ref "J1") (pin "21") (pinfunction "21_21") (pintype "passive"))
      (node (ref "U1") (pin "22") (pinfunction "GPIO18/RTC_GPIO18/U1RXD/ADC2_CH7/CLK_OUT3_22") (pintype "passive"))
    )
    (net (code "42") (name "/GPIO21") (class "Default")
      (node (ref "J2") (pin "19") (pinfunction "19_19") (pintype "passive"))
      (node (ref "U1") (pin "25") (pinfunction "GPIO21/RTC_GPIO21_25") (pintype "passive"))
    )
    (net (code "43") (name "/GPIO26") (class "Default")
      (node (ref "J2") (pin "18") (pinfunction "18_18") (pintype "passive"))
      (node (ref "U1") (pin "26") (pinfunction "GPIO26/SPICS1_26") (pintype "passive"))
    )
    (net (code "44") (name "/GPIO33") (class "Default")
      (node (ref "J2") (pin "17") (pinfunction "17_17") (pintype "passive"))
      (node (ref "U1") (pin "28") (pinfunction "GPIO33/SPIIO4/FSPIHD/SUBSPIHD_28") (pintype "passive"))
    )
    (net (code "45") (name "/GPIO34") (class "Default")
      (node (ref "J2") (pin "16") (pinfunction "16_16") (pintype "passive"))
      (node (ref "U1") (pin "29") (pinfunction "GPIO34/SPIIO5/FSPICS0/SUBSPICS0_29") (pintype "passive"))
    )
    (net (code "46") (name "/GPIO35") (class "Default")
      (node (ref "J2") (pin "15") (pinfunction "15_15") (pintype "passive"))
      (node (ref "U1") (pin "31") (pinfunction "GPIO35/SPIIO6/FSPID/SUBSPID_31") (pintype "passive"))
    )
    (net (code "47") (name "/GPIO36") (class "Default")
      (node (ref "J2") (pin "14") (pinfunction "14_14") (pintype "passive"))
      (node (ref "U1") (pin "32") (pinfunction "GPIO36/SPIIO7/FSPICLK/SUBSPICLK_32") (pintype "passive"))
    )
    (net (code "48") (name "/GPIO37") (class "Default")
      (node (ref "J2") (pin "13") (pinfunction "13_13") (pintype "passive"))
      (node (ref "U1") (pin "33") (pinfunction "GPIO37/SPIDQS/FSPIQ/SUBSPIQ_33") (pintype "passive"))
    )
    (net (code "49") (name "/GPIO38") (class "Default")
      (node (ref "J2") (pin "12") (pinfunction "12_12") (pintype "passive"))
      (node (ref "U1") (pin "34") (pinfunction "GPIO38/FSPIWP/SUBSPIWP_34") (pintype "passive"))
    )
    (net (code "50") (name "/GPIO39") (class "Default")
      (node (ref "J2") (pin "11") (pinfunction "11_11") (pintype "passive"))
      (node (ref "U1") (pin "35") (pinfunction "MTCK/GPIO39/CLK_OUT3/SUBSPICS1_35") (pintype "passive"))
    )
    (net (code "51") (name "/GPIO40") (class "Default")
      (node (ref "J2") (pin "10") (pinfunction "10_10") (pintype "passive"))
      (node (ref "U1") (pin "36") (pinfunction "MTDO/GPIO40/CLK_OUT2_36") (pintype "passive"))
    )
    (net (code "52") (name "/GPIO41") (class "Default")
      (node (ref "J2") (pin "9") (pinfunction "9_9") (pintype "passive"))
      (node (ref "U1") (pin "37") (pinfunction "MTDI/GPIO41/CLK_OUT1_37") (pintype "passive"))
    )
    (net (code "53") (name "/GPIO42") (class "Default")
      (node (ref "J2") (pin "8") (pinfunction "8_8") (pintype "passive"))
      (node (ref "U1") (pin "38") (pinfunction "MTMS/GPIO42_38") (pintype "passive"))
    )
    (net (code "54") (name "/GPIO45") (class "Default")
      (node (ref "J2") (pin "5") (pinfunction "5_5") (pintype "passive"))
      (node (ref "U1") (pin "41") (pinfunction "GPIO45_41") (pintype "passive"))
    )
    (net (code "55") (name "/GPIO46") (class "Default")
      (node (ref "J2") (pin "4") (pinfunction "4_4") (pintype "passive"))
      (node (ref "U1") (pin "44") (pinfunction "GPIO46_44") (pintype "passive"))
    )
    (net (code "56") (name "/GPIO47") (class "Default")
      (node (ref "J2") (pin "23") (pinfunction "23_23") (pintype "passive"))
      (node (ref "U1") (pin "27") (pinfunction "GPIO47/SPICLK_P_DIFF/SUBSPICLK_P_DIFF_27") (pintype "passive"))
    )
    (net (code "57") (name "/GPIO48") (class "Default")
      (node (ref "J2") (pin "22") (pinfunction "22_22") (pintype "passive"))
      (node (ref "U1") (pin "30") (pinfunction "GPIO48/SPICLK_N_DIFF/SUBSPICLK_N_DIFF_30") (pintype "passive"))
    )
    (net (code "58") (name "/RTS_FTDI") (class "Default")
      (node (ref "Q1") (pin "2") (pinfunction "E_2") (pintype "passive"))
      (node (ref "R17") (pin "2") (pinfunction "2_2") (pintype "passive"))
      (node (ref "U2") (pin "19") (pinfunction "~{RTS}_19") (pintype "passive"))
    )
    (net (code "59") (name "/RXD_FTDI") (class "Default")
      (node (ref "R19") (pin "2") (pinfunction "2_2") (pintype "passive"))
      (node (ref "U2") (pin "1") (pinfunction "RXD_1") (pintype "passive"))
    )
    (net (code "60") (name "/TXD_FTDI") (class "Default")
      (node (ref "R20") (pin "2") (pinfunction "2_2") (pintype "passive"))
      (node (ref "U2") (pin "17") (pinfunction "TXD_17") (pintype "passive"))
    )
    (net (code "61") (name "/U0RXD") (class "Default")
      (node (ref "J2") (pin "6") (pinfunction "6_6") (pintype "passive"))
      (node (ref "R20") (pin "1") (pinfunction "1_1") (pintype "passive"))
      (node (ref "U1") (pin "40") (pinfunction "U0RXD/GPIO44/CLK_OUT2_40") (pintype "passive"))
    )
    (net (code "62") (name "/U0TXD") (class "Default")
      (node (ref "J2") (pin "7") (pinfunction "7_7") (pintype "passive"))
      (node (ref "R19") (pin "1") (pinfunction "1_1") (pintype "passive"))
      (node (ref "U1") (pin "39") (pinfunction "U0TXD/GPIO43/CLK_OUT1_39") (pintype "passive"))
    )
    (net (code "63") (name "/VBUS_SENSE") (class "Default")
      (node (ref "R10") (pin "1") (pinfunction "1_1") (pintype "passive"))
      (node (ref "R13") (pin "2") (pinfunction "2_2") (pintype "passive"))
      (node (ref "U2") (pin "16") (pinfunction "CBUS3_16") (pintype "passive"))
    )
    (net (code "64") (name "GND") (class "Default")
      (node (ref "C1") (pin "1") (pinfunction "1_1") (pintype "passive"))
      (node (ref "C10") (pin "1") (pinfunction "1_1") (pintype "passive"))
      (node (ref "C11") (pin "1") (pinfunction "1_1") (pintype "passive"))
      (node (ref "C12") (pin "1") (pinfunction "1_1") (pintype "passive"))
      (node (ref "C13") (pin "1") (pinfunction "1_1") (pintype "passive"))
      (node (ref "C14") (pin "1") (pinfunction "1_1") (pintype "passive"))
      (node (ref "C15") (pin "1") (pinfunction "1_1") (pintype "passive"))
      (node (ref "C16") (pin "2") (pinfunction "2_2") (pintype "passive"))
      (node (ref "C17") (pin "1") (pinfunction "1_1") (pintype "passive"))
      (node (ref "C2") (pin "1") (pinfunction "1_1") (pintype "passive"))
      (node (ref "C3") (pin "1") (pinfunction "1_1") (pintype "passive"))
      (node (ref "C4") (pin "1") (pinfunction "1_1") (pintype "passive"))
      (node (ref "C5") (pin "1") (pinfunction "1_1") (pintype "passive"))
      (node (ref "C6") (pin "1") (pinfunction "1_1") (pintype "passive"))
      (node (ref "C7") (pin "1") (pinfunction "1_1") (pintype "passive"))
      (node (ref "C8") (pin "1") (pinfunction "1_1") (pintype "passive"))
      (node (ref "C9") (pin "1") (pinfunction "1_1") (pintype "passive"))
      (node (ref "D1") (pin "1") (pinfunction "1_1") (pintype "passive"))
      (node (ref "D3") (pin "2") (pinfunction "2_2") (pintype "passive"))
      (node (ref "D4") (pin "2") (pinfunction "2_2") (pintype "passive"))
      (node (ref "D5") (pin "2") (pinfunction "2_2") (pintype "passive"))
      (node (ref "D6") (pin "2") (pinfunction "2_2") (pintype "passive"))
      (node (ref "D7") (pin "2") (pinfunction "2_2") (pintype "passive"))
      (node (ref "D8") (pin "2") (pinfunction "2_2") (pintype "passive"))
      (node (ref "J1") (pin "1") (pinfunction "1_1") (pintype "passive"))
      (node (ref "J1") (pin "23") (pinfunction "23_23") (pintype "passive"))
      (node (ref "J2") (pin "2") (pinfunction "2_2") (pintype "passive"))
      (node (ref "J2") (pin "24") (pinfunction "24_24") (pintype "passive"))
      (node (ref "J3") (pin "A1B12") (pinfunction "GND_A1B12_A1B12") (pintype "passive"))
      (node (ref "J3") (pin "B1A12") (pinfunction "GND_B1A12_B1A12") (pintype "passive"))
      (node (ref "J3") (pin "S1") (pinfunction "SHIELD_1_S1") (pintype "passive"))
      (node (ref "J3") (pin "S2") (pinfunction "SHIELD_2_S2") (pintype "passive"))
      (node (ref "J3") (pin "S3") (pinfunction "SHIELD_3_S3") (pintype "passive"))
      (node (ref "J3") (pin "S4") (pinfunction "SHIELD_4_S4") (pintype "passive"))
      (node (ref "J4") (pin "A1B12") (pinfunction "GND_A1B12_A1B12") (pintype "passive"))
      (node (ref "J4") (pin "B1A12") (pinfunction "GND_B1A12_B1A12") (pintype "passive"))
      (node (ref "J4") (pin "S1") (pinfunction "SHIELD_1_S1") (pintype "passive"))
      (node (ref "J4") (pin "S2") (pinfunction "SHIELD_2_S2") (pintype "passive"))
      (node (ref "J4") (pin "S3") (pinfunction "SHIELD_3_S3") (pintype "passive"))
      (node (ref "J4") (pin "S4") (pinfunction "SHIELD_4_S4") (pintype "passive"))
      (node (ref "R11") (pin "1") (pinfunction "1_1") (pintype "passive"))
      (node (ref "R12") (pin "1") (pinfunction "1_1") (pintype "passive"))
      (node (ref "R13") (pin "1") (pinfunction "1_1") (pintype "passive"))
      (node (ref "R14") (pin "1") (pinfunction "1_1") (pintype "passive"))
      (node (ref "R15") (pin "1") (pinfunction "1_1") (pintype "passive"))
      (node (ref "R9") (pin "2") (pinfunction "2_2") (pintype "passive"))
      (node (ref "SW1") (pin "3") (pinfunction "3_3") (pintype "passive"))
      (node (ref "SW1") (pin "4") (pinfunction "4_4") (pintype "passive"))
      (node (ref "SW2") (pin "3") (pinfunction "3_3") (pintype "passive"))
      (node (ref "SW2") (pin "4") (pinfunction "4_4") (pintype "passive"))
      (node (ref "U1") (pin "1") (pinfunction "GND_01_1") (pintype "passive"))
      (node (ref "U1") (pin "2") (pinfunction "GND_02_2") (pintype "passive"))
      (node (ref "U1") (pin "42") (pinfunction "GND_42") (pintype "passive"))
      (node (ref "U1") (pin "43") (pinfunction "GND_43") (pintype "passive"))
      (node (ref "U1") (pin "46") (pinfunction "GND_46_46") (pintype "passive"))
      (node (ref "U1") (pin "47") (pinfunction "GND_47_47") (pintype "passive"))
      (node (ref "U1") (pin "48") (pinfunction "GND_48_48") (pintype "passive"))
      (node (ref "U1") (pin "49") (pinfunction "GND_49_49") (pintype "passive"))
      (node (ref "U1") (pin "50") (pinfunction "GND_50_50") (pintype "passive"))
      (node (ref "U1") (pin "51") (pinfunction "GND_51_51") (pintype "passive"))
      (node (ref "U1") (pin "52") (pinfunction "GND_52_52") (pintype "passive"))
      (node (ref "U1") (pin "53") (pinfunction "GND_53_53") (pintype "passive"))
      (node (ref "U1") (pin "54") (pinfunction "GND_54_54") (pintype "passive"))
      (node (ref "U1") (pin "55") (pinfunction "GND_55_55") (pintype "passive"))
      (node (ref "U1") (pin "56") (pinfunction "GND_56_56") (pintype "passive"))
      (node (ref "U1") (pin "57") (pinfunction "GND_57_57") (pintype "passive"))
      (node (ref "U1") (pin "58") (pinfunction "GND_58_58") (pintype "passive"))
      (node (ref "U1") (pin "59") (pinfunction "GND_59_59") (pintype "passive"))
      (node (ref "U1") (pin "60") (pinfunction "GND_60_60") (pintype "passive"))
      (node (ref "U1") (pin "61") (pinfunction "GND_61_61") (pintype "passive"))
      (node (ref "U1") (pin "62") (pinfunction "GND_62_62") (pintype "passive"))
      (node (ref "U1") (pin "63") (pinfunction "GND_63_63") (pintype "passive"))
      (node (ref "U1") (pin "64") (pinfunction "GND_64_64") (pintype "passive"))
      (node (ref "U1") (pin "65") (pinfunction "GND_65_65") (pintype "passive"))
      (node (ref "U1") (pin "66") (pinfunction "GND_66_66") (pintype "passive"))
      (node (ref "U1") (pin "67") (pinfunction "GND_67_67") (pintype "passive"))
      (node (ref "U1") (pin "68") (pinfunction "GND_68_68") (pintype "passive"))
      (node (ref "U1") (pin "69") (pinfunction "GND_69_69") (pintype "passive"))
      (node (ref "U1") (pin "70") (pinfunction "GND_70_70") (pintype "passive"))
      (node (ref "U1") (pin "71") (pinfunction "GND_71_71") (pintype "passive"))
      (node (ref "U1") (pin "72") (pinfunction "GND_72_72") (pintype "passive"))
      (node (ref "U1") (pin "73") (pinfunction "GND_73_73") (pintype "passive"))
      (node (ref "U2") (pin "13") (pinfunction "GND_13") (pintype "passive"))
      (node (ref "U2") (pin "21") (pinfunction "GND_21") (pintype "passive"))
      (node (ref "U2") (pin "3") (pinfunction "GND_3") (pintype "passive"))
      (node (ref "U3") (pin "2") (pinfunction "GND_2") (pintype "power_in"))
      (node (ref "U3") (pin "4") (pinfunction "GND_4") (pintype "power_in"))
    )
    (net (code "65") (name "Net-(D1-Pad2)") (class "Default")
      (node (ref "D1") (pin "2") (pinfunction "2_2") (pintype "passive"))
      (node (ref "R4") (pin "1") (pinfunction "1_1") (pintype "passive"))
    )
    (net (code "66") (name "Net-(D2-Pad2)") (class "Default")
      (node (ref "D2") (pin "2") (pinfunction "2_2") (pintype "passive"))
      (node (ref "R5") (pin "1") (pinfunction "1_1") (pintype "passive"))
    )
    (net (code "67") (name "Net-(J3-CC1)") (class "Default")
      (node (ref "J3") (pin "A5") (pinfunction "CC1_A5") (pintype "passive"))
      (node (ref "R12") (pin "2") (pinfunction "2_2") (pintype "passive"))
    )
    (net (code "68") (name "Net-(J3-CC2)") (class "Default")
      (node (ref "J3") (pin "B5") (pinfunction "CC2_B5") (pintype "passive"))
      (node (ref "R11") (pin "2") (pinfunction "2_2") (pintype "passive"))
    )
    (net (code "69") (name "Net-(J4-CC1)") (class "Default")
      (node (ref "J4") (pin "A5") (pinfunction "CC1_A5") (pintype "passive"))
      (node (ref "R15") (pin "2") (pinfunction "2_2") (pintype "passive"))
    )
    (net (code "70") (name "Net-(J4-CC2)") (class "Default")
      (node (ref "J4") (pin "B5") (pinfunction "CC2_B5") (pintype "passive"))
      (node (ref "R14") (pin "2") (pinfunction "2_2") (pintype "passive"))
    )
    (net (code "71") (name "Net-(Q1-B)") (class "Default")
      (node (ref "Q1") (pin "1") (pinfunction "B_1") (pintype "passive"))
      (node (ref "R16") (pin "1") (pinfunction "1_1") (pintype "passive"))
    )
    (net (code "72") (name "Net-(Q2-B)") (class "Default")
      (node (ref "Q2") (pin "1") (pinfunction "B_1") (pintype "passive"))
      (node (ref "R17") (pin "1") (pinfunction "1_1") (pintype "passive"))
    )
    (net (code "73") (name "Net-(U2-CBUS0)") (class "Default")
      (node (ref "R9") (pin "1") (pinfunction "1_1") (pintype "passive"))
      (node (ref "U2") (pin "15") (pinfunction "CBUS0_15") (pintype "passive"))
    )
    (net (code "74") (name "unconnected-(J1-Pad24)") (class "Default")
      (node (ref "J1") (pin "24") (pinfunction "24_24") (pintype "passive+no_connect"))
    )
    (net (code "75") (name "unconnected-(J3-ABU2-PadB8)") (class "Default")
      (node (ref "J3") (pin "B8") (pinfunction "ABU2_B8") (pintype "passive+no_connect"))
    )
    (net (code "76") (name "unconnected-(J3-SBU1-PadA8)") (class "Default")
      (node (ref "J3") (pin "A8") (pinfunction "SBU1_A8") (pintype "passive+no_connect"))
    )
    (net (code "77") (name "unconnected-(J4-ABU2-PadB8)") (class "Default")
      (node (ref "J4") (pin "B8") (pinfunction "ABU2_B8") (pintype "passive+no_connect"))
    )
    (net (code "78") (name "unconnected-(J4-SBU1-PadA8)") (class "Default")
      (node (ref "J4") (pin "A8") (pinfunction "SBU1_A8") (pintype "passive+no_connect"))
    )
    (net (code "79") (name "unconnected-(U2-CBUS1-Pad14)") (class "Default")
      (node (ref "U2") (pin "14") (pinfunction "CBUS1_14") (pintype "passive+no_connect"))
    )
    (net (code "80") (name "unconnected-(U2-CBUS2-Pad7)") (class "Default")
      (node (ref "U2") (pin "7") (pinfunction "CBUS2_7") (pintype "passive+no_connect"))
    )
    (net (code "81") (name "unconnected-(U2-~{CTS}-Pad6)") (class "Default")
      (node (ref "U2") (pin "6") (pinfunction "~{CTS}_6") (pintype "passive+no_connect"))
    )
    (net (code "82") (name "unconnected-(U2-~{DCD}-Pad5)") (class "Default")
      (node (ref "U2") (pin "5") (pinfunction "~{DCD}_5") (pintype "passive+no_connect"))
    )
    (net (code "83") (name "unconnected-(U2-~{DSR}-Pad4)") (class "Default")
      (node (ref "U2") (pin "4") (pinfunction "~{DSR}_4") (pintype "passive+no_connect"))
    )
    (net (code "84") (name "unconnected-(U2-~{RI}-Pad2)") (class "Default")
      (node (ref "U2") (pin "2") (pinfunction "~{RI}_2") (pintype "passive+no_connect"))
    )
  )
)
